# Traiak.net
KiCad netlist of a schematic drawn in Altium Designer
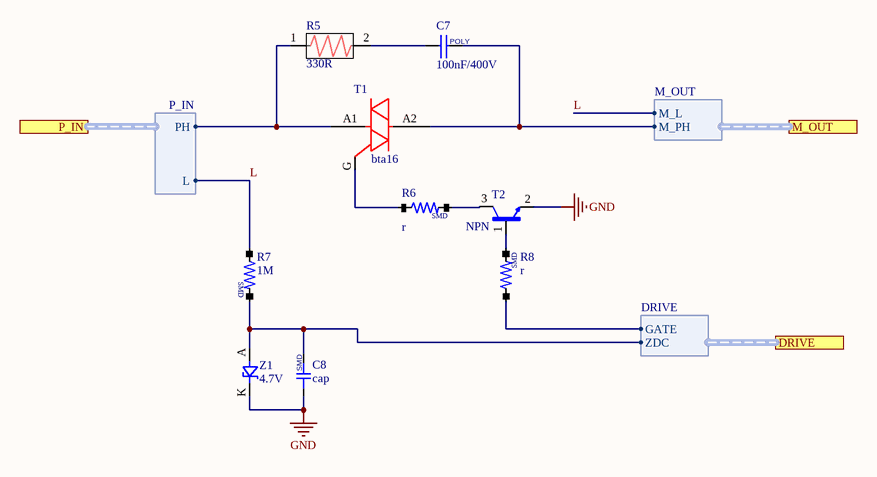
[diagram p0: Traiak.SchDoc]

(export (version "E")
  (design (tool "Eeschema 10.0.6"))
  (components
    (comp (ref "C7")
      (value "100nF/400V")
      (footprint "CAP/100nF/275V/poly")
      (libsource (lib "kave-eng-pro") (part "cap-poly"))
    )
    (comp (ref "C8") (value "cap") (footprint "CAP-0805") (libsource (lib "kave-eng-pro") (part "cap_smd")))
    (comp (ref "R5")
      (value "330R")
      (footprint "RES/1W")
      (libsource (lib "kave-eng-pro") (part "RES/{gt}=1W"))
    )
    (comp (ref "R6") (value "r") (footprint "RES/0805") (libsource (lib "") (part "RES/SMD_1")))
    (comp (ref "R7") (value "1M") (footprint "RES/0805") (libsource (lib "") (part "RES/SMD_2")))
    (comp (ref "R8") (value "r") (footprint "RES/0805") (libsource (lib "kave-eng-pro") (part "RES/SMD")))
    (comp (ref "T1") (value "bta16") (footprint "bta16") (libsource (lib "kave-eng-pro") (part "bta16")))
    (comp (ref "T2") (value "NPN") (footprint "SOT23") (libsource (lib "kave-eng-pro") (part "NPN")))
    (comp (ref "Z1")
      (value "4.7V")
      (footprint "DIOD/RS1J")
      (libsource (lib "kave-eng-pro") (part "zener-0.5w"))
    )
  )
  (nets
    (net (code "4") (name "/GATE") (class "Default")
      (node (ref "R8") (pin "1") (pinfunction "1_1") (pintype "passive"))
    )
    (net (code "5") (name "/L") (class "Default")
      (node (ref "R7") (pin "1") (pinfunction "1_1") (pintype "passive"))
    )
    (net (code "6") (name "/M_PH") (class "Default")
      (node (ref "C7") (pin "2") (pintype "passive"))
      (node (ref "T1") (pin "A2") (pintype "passive"))
    )
    (net (code "7") (name "/PH") (class "Default")
      (node (ref "R5") (pin "1") (pintype "passive"))
      (node (ref "T1") (pin "A1") (pintype "passive"))
    )
    (net (code "8") (name "/ZDC") (class "Default")
      (node (ref "C8") (pin "2") (pintype "passive"))
      (node (ref "R7") (pin "2") (pinfunction "2_2") (pintype "passive"))
      (node (ref "Z1") (pin "A") (pintype "passive"))
    )
    (net (code "12") (name "GND") (class "Default")
      (node (ref "C8") (pin "1") (pintype "passive"))
      (node (ref "T2") (pin "2") (pinfunction "E_2") (pintype "passive"))
      (node (ref "Z1") (pin "K") (pintype "passive"))
    )
    (net (code "13") (name "Net-(C7-Pad1)") (class "Default")
      (node (ref "C7") (pin "1") (pintype "passive"))
      (node (ref "R5") (pin "2") (pintype "passive"))
    )
    (net (code "14") (name "Net-(R6-Pad1)") (class "Default")
      (node (ref "R6") (pin "1") (pinfunction "1_1") (pintype "passive"))
      (node (ref "T1") (pin "G") (pintype "passive"))
    )
    (net (code "15") (name "Net-(T2-B)") (class "Default")
      (node (ref "R8") (pin "2") (pinfunction "2_2") (pintype "passive"))
      (node (ref "T2") (pin "1") (pinfunction "B_1") (pintype "passive"))
    )
    (net (code "16") (name "Net-(T2-C)") (class "Default")
      (node (ref "R6") (pin "2") (pinfunction "2_2") (pintype "passive"))
      (node (ref "T2") (pin "3") (pinfunction "C_3") (pintype "passive"))
    )
  )
)
